# queso_dip_v4_7.net
KiCad netlist of a schematic drawn in EAGLE
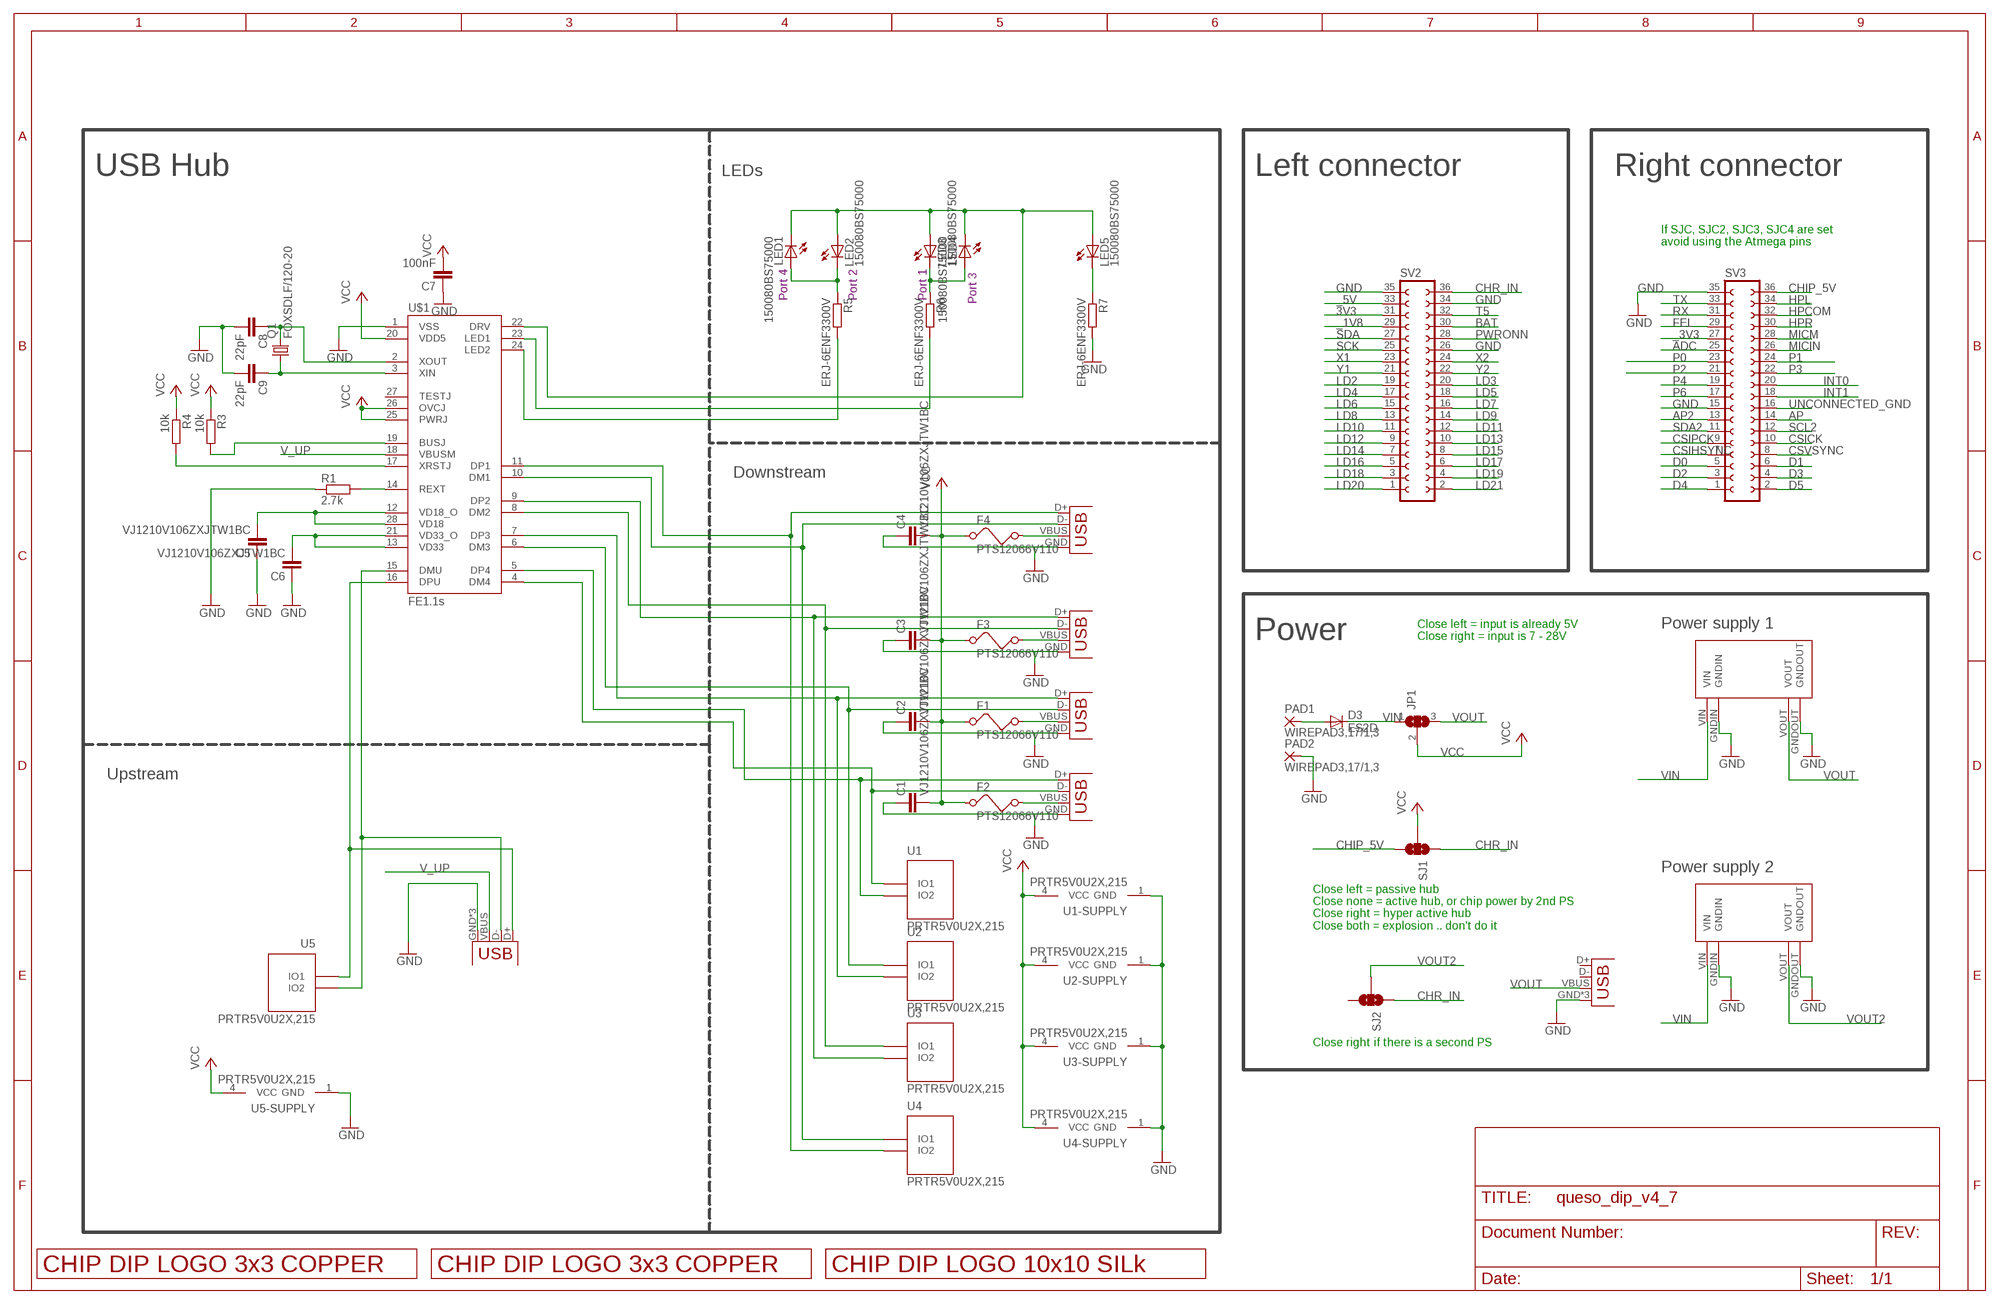
[diagram p0: schematic, sheet 1]

(export (version "E")
  (design (tool "Eeschema 10.0.6"))
  (components
    (comp (ref "C1")
      (value "VJ1210V106ZXJTW1BC")
      (footprint "eagle-import:C1210")
      (libsource (lib "eagle-import") (part "C-EUC1210"))
    )
    (comp (ref "C2")
      (value "VJ1210V106ZXJTW1BC")
      (footprint "eagle-import:C1210")
      (libsource (lib "eagle-import") (part "C-EUC1210"))
    )
    (comp (ref "C3")
      (value "VJ1210V106ZXJTW1BC")
      (footprint "eagle-import:C1210")
      (libsource (lib "eagle-import") (part "C-EUC1210"))
    )
    (comp (ref "C4")
      (value "VJ1210V106ZXJTW1BC")
      (footprint "eagle-import:C1210")
      (libsource (lib "eagle-import") (part "C-EUC1210"))
    )
    (comp (ref "C5")
      (value "VJ1210V106ZXJTW1BC")
      (footprint "eagle-import:C1210")
      (libsource (lib "eagle-import") (part "C-EUC1210"))
    )
    (comp (ref "C6")
      (value "VJ1210V106ZXJTW1BC")
      (footprint "eagle-import:C1210")
      (libsource (lib "eagle-import") (part "C-EUC1210"))
    )
    (comp (ref "C7")
      (value "100nF")
      (footprint "eagle-import:C0805")
      (libsource (lib "eagle-import") (part "C-EUC0805"))
    )
    (comp (ref "C8")
      (value "22pF")
      (footprint "eagle-import:C0805")
      (libsource (lib "eagle-import") (part "C-EUC0805"))
    )
    (comp (ref "C9")
      (value "22pF")
      (footprint "eagle-import:C0805")
      (libsource (lib "eagle-import") (part "C-EUC0805"))
    )
    (comp (ref "D3")
      (value "ES2D")
      (footprint "eagle-import:SMB")
      (libsource (lib "eagle-import") (part "ES2D"))
    )
    (comp (ref "F1")
      (value "PTS12066V110")
      (footprint "eagle-import:1210")
      (libsource (lib "eagle-import") (part "FUSED"))
    )
    (comp (ref "F2")
      (value "PTS12066V110")
      (footprint "eagle-import:1210")
      (libsource (lib "eagle-import") (part "FUSED"))
    )
    (comp (ref "F3")
      (value "PTS12066V110")
      (footprint "eagle-import:1210")
      (libsource (lib "eagle-import") (part "FUSED"))
    )
    (comp (ref "F4")
      (value "PTS12066V110")
      (footprint "eagle-import:1210")
      (libsource (lib "eagle-import") (part "FUSED"))
    )
    (comp (ref "JP1")
      (value "SJ2W")
      (footprint "eagle-import:SJ_2")
      (libsource (lib "eagle-import") (part "SJ2W"))
    )
    (comp (ref "LED1")
      (value "150080BS75000")
      (footprint "eagle-import:CHIP-LED0805")
      (libsource (lib "eagle-import") (part "LEDCHIP-LED0805"))
    )
    (comp (ref "LED2")
      (value "150080BS75000")
      (footprint "eagle-import:CHIP-LED0805")
      (libsource (lib "eagle-import") (part "LEDCHIP-LED0805"))
    )
    (comp (ref "LED3")
      (value "150080BS75000")
      (footprint "eagle-import:CHIP-LED0805")
      (libsource (lib "eagle-import") (part "LEDCHIP-LED0805"))
    )
    (comp (ref "LED4")
      (value "150080BS75000")
      (footprint "eagle-import:CHIP-LED0805")
      (libsource (lib "eagle-import") (part "LEDCHIP-LED0805"))
    )
    (comp (ref "LED5")
      (value "150080BS75000")
      (footprint "eagle-import:CHIP-LED0805")
      (libsource (lib "eagle-import") (part "LEDCHIP-LED0805"))
    )
    (comp (ref "PAD1")
      (value "WIREPAD3,17/1,3")
      (footprint "eagle-import:3,17_1,3")
      (libsource (lib "eagle-import") (part "WIREPAD3,17/1,3"))
    )
    (comp (ref "PAD2")
      (value "WIREPAD3,17/1,3")
      (footprint "eagle-import:3,17_1,3")
      (libsource (lib "eagle-import") (part "WIREPAD3,17/1,3"))
    )
    (comp (ref "Q1")
      (value "FOXSDLF/120-20")
      (footprint "eagle-import:SM49")
      (libsource (lib "eagle-import") (part "CRYSTALSM49"))
    )
    (comp (ref "R1")
      (value "2.7k")
      (footprint "eagle-import:R0805")
      (libsource (lib "eagle-import") (part "R-EU_R0805"))
    )
    (comp (ref "R3")
      (value "10k")
      (footprint "eagle-import:R0805")
      (libsource (lib "eagle-import") (part "R-EU_R0805"))
    )
    (comp (ref "R4")
      (value "10k")
      (footprint "eagle-import:R0805")
      (libsource (lib "eagle-import") (part "R-EU_R0805"))
    )
    (comp (ref "R5")
      (value "ERJ-6ENF3300V")
      (footprint "eagle-import:R0805")
      (libsource (lib "eagle-import") (part "R-EU_R0805"))
    )
    (comp (ref "R6")
      (value "ERJ-6ENF3300V")
      (footprint "eagle-import:R0805")
      (libsource (lib "eagle-import") (part "R-EU_R0805"))
    )
    (comp (ref "R7")
      (value "ERJ-6ENF3300V")
      (footprint "eagle-import:R0805")
      (libsource (lib "eagle-import") (part "R-EU_R0805"))
    )
    (comp (ref "SJ1")
      (value "SOLDERJUMPER_2WAYT")
      (footprint "eagle-import:SJ_2")
      (libsource (lib "eagle-import") (part "SOLDERJUMPER_2WAYT"))
    )
    (comp (ref "SJ2")
      (value "SOLDERJUMPER_2WAYT")
      (footprint "eagle-import:SJ_2")
      (libsource (lib "eagle-import") (part "SOLDERJUMPER_2WAYT"))
    )
    (comp (ref "SV2")
      (value "FE18-2")
      (footprint "eagle-import:FE18-2")
      (libsource (lib "eagle-import") (part "FE18-2"))
    )
    (comp (ref "SV3")
      (value "FE18-2")
      (footprint "eagle-import:FE18-2")
      (libsource (lib "eagle-import") (part "FE18-2"))
    )
    (comp (ref "U$1")
      (value "FE1.1S")
      (footprint "eagle-import:FE1.1S_SSOP-28")
      (libsource (lib "eagle-import") (part "FE1.1S"))
    )
    (comp (ref "U$2")
      (value "LOGO_3X3_COPPER")
      (footprint "eagle-import:LOGO_3X3_COPPER")
      (libsource (lib "eagle-import") (part "LOGO_3X3_COPPER"))
    )
    (comp (ref "U$3")
      (value "MP1584EN")
      (footprint "eagle-import:MP1584EN")
      (libsource (lib "eagle-import") (part "MP1584EN"))
    )
    (comp (ref "U$4")
      (value "LOGO_3X3_COPPER")
      (footprint "eagle-import:LOGO_3X3_COPPER")
      (libsource (lib "eagle-import") (part "LOGO_3X3_COPPER"))
    )
    (comp (ref "U$5")
      (value "LOGO_10X10_SILK")
      (footprint "eagle-import:LOGO_10X10_SILK")
      (libsource (lib "eagle-import") (part "LOGO_10X10_SILK"))
    )
    (comp (ref "U$9")
      (value "MP1584EN")
      (footprint "eagle-import:MP1584EN")
      (libsource (lib "eagle-import") (part "MP1584EN"))
    )
    (comp (ref "U1")
      (value "PRTR5V0U2X,215")
      (footprint "eagle-import:SOT-143B")
      (fields (field (name "MANUFACTURER") "NXP Semiconductors"))
      (libsource (lib "eagle-import") (part "PRTR5V0U2X?"))
    )
    (comp (ref "U2")
      (value "PRTR5V0U2X,215")
      (footprint "eagle-import:SOT-143B")
      (fields (field (name "MANUFACTURER") "NXP Semiconductors"))
      (libsource (lib "eagle-import") (part "PRTR5V0U2X?"))
    )
    (comp (ref "U3")
      (value "PRTR5V0U2X,215")
      (footprint "eagle-import:SOT-143B")
      (fields (field (name "MANUFACTURER") "NXP Semiconductors"))
      (libsource (lib "eagle-import") (part "PRTR5V0U2X?"))
    )
    (comp (ref "U4")
      (value "PRTR5V0U2X,215")
      (footprint "eagle-import:SOT-143B")
      (fields (field (name "MANUFACTURER") "NXP Semiconductors"))
      (libsource (lib "eagle-import") (part "PRTR5V0U2X?"))
    )
    (comp (ref "U5")
      (value "PRTR5V0U2X,215")
      (footprint "eagle-import:SOT-143B")
      (fields (field (name "MANUFACTURER") "NXP Semiconductors"))
      (libsource (lib "eagle-import") (part "PRTR5V0U2X?"))
    )
    (comp (ref "USB")
      (value "USBUSB-MICROB-SMT-DIP")
      (footprint "eagle-import:USB-MICROB-SMT-DIP")
      (libsource (lib "eagle-import") (part "USBUSB-MICROB-SMT-DIP"))
    )
    (comp (ref "USB1")
      (value "USBUSB-MICROB-SMT-DIP")
      (footprint "eagle-import:USB-MICROB-SMT-DIP")
      (libsource (lib "eagle-import") (part "USBUSB-MICROB-SMT-DIP"))
    )
    (comp (ref "X1")
      (value "USB-A-S")
      (footprint "eagle-import:USB-A-S")
      (libsource (lib "eagle-import") (part "con-usb_USB-A-S"))
    )
    (comp (ref "X2")
      (value "USB-A-S")
      (footprint "eagle-import:USB-A-S")
      (libsource (lib "eagle-import") (part "con-usb_USB-A-S"))
    )
    (comp (ref "X3")
      (value "USB-A-S")
      (footprint "eagle-import:USB-A-S")
      (libsource (lib "eagle-import") (part "con-usb_USB-A-S"))
    )
    (comp (ref "X4")
      (value "USB-A-S")
      (footprint "eagle-import:USB-A-S")
      (libsource (lib "eagle-import") (part "con-usb_USB-A-S"))
    )
  )
  (nets
    (net (code "1") (name "/3V3") (class "Default")
      (node (ref "SV2") (pin "31") (pinfunction "31_31") (pintype "passive"))
    )
    (net (code "2") (name "/ADC") (class "Default")
      (node (ref "SV3") (pin "25") (pinfunction "25_25") (pintype "passive"))
    )
    (net (code "3") (name "/AP") (class "Default")
      (node (ref "SV3") (pin "14") (pinfunction "14_14") (pintype "passive"))
    )
    (net (code "4") (name "/AP2") (class "Default")
      (node (ref "SV3") (pin "13") (pinfunction "13_13") (pintype "passive"))
    )
    (net (code "5") (name "/BAT") (class "Default")
      (node (ref "SV2") (pin "30") (pinfunction "30_30") (pintype "passive"))
    )
    (net (code "6") (name "/CHIP_5V") (class "Default")
      (node (ref "SJ1") (pin "3") (pinfunction "3_3") (pintype "passive"))
      (node (ref "SV3") (pin "36") (pinfunction "36_36") (pintype "passive"))
    )
    (net (code "7") (name "/CHR_IN") (class "Default")
      (node (ref "SJ1") (pin "1") (pinfunction "1_1") (pintype "passive"))
      (node (ref "SJ2") (pin "1") (pinfunction "1_1") (pintype "passive"))
      (node (ref "SV2") (pin "36") (pinfunction "36_36") (pintype "passive"))
    )
    (net (code "8") (name "/CSICK") (class "Default")
      (node (ref "SV3") (pin "10") (pinfunction "10_10") (pintype "passive"))
    )
    (net (code "9") (name "/CSIHSYNC") (class "Default")
      (node (ref "SV3") (pin "7") (pinfunction "7_7") (pintype "passive"))
    )
    (net (code "10") (name "/CSIPCK") (class "Default")
      (node (ref "SV3") (pin "9") (pinfunction "9_9") (pintype "passive"))
    )
    (net (code "11") (name "/CSVSYNC") (class "Default")
      (node (ref "SV3") (pin "8") (pinfunction "8_8") (pintype "passive"))
    )
    (net (code "12") (name "/D0") (class "Default")
      (node (ref "SV3") (pin "5") (pinfunction "5_5") (pintype "passive"))
    )
    (net (code "13") (name "/D1") (class "Default")
      (node (ref "SV3") (pin "6") (pinfunction "6_6") (pintype "passive"))
    )
    (net (code "14") (name "/D2") (class "Default")
      (node (ref "SV3") (pin "3") (pinfunction "3_3") (pintype "passive"))
    )
    (net (code "15") (name "/D3") (class "Default")
      (node (ref "SV3") (pin "4") (pinfunction "4_4") (pintype "passive"))
    )
    (net (code "16") (name "/D4") (class "Default")
      (node (ref "SV3") (pin "1") (pinfunction "1_1") (pintype "passive"))
    )
    (net (code "17") (name "/D5") (class "Default")
      (node (ref "SV3") (pin "2") (pinfunction "2_2") (pintype "passive"))
    )
    (net (code "18") (name "/FEL") (class "Default")
      (node (ref "SV3") (pin "29") (pinfunction "29_29") (pintype "passive"))
    )
    (net (code "19") (name "/HPCOM") (class "Default")
      (node (ref "SV3") (pin "32") (pinfunction "32_32") (pintype "passive"))
    )
    (net (code "20") (name "/HPL") (class "Default")
      (node (ref "SV3") (pin "34") (pinfunction "34_34") (pintype "passive"))
    )
    (net (code "21") (name "/HPR") (class "Default")
      (node (ref "SV3") (pin "30") (pinfunction "30_30") (pintype "passive"))
    )
    (net (code "22") (name "/INT0") (class "Default")
      (node (ref "SV3") (pin "20") (pinfunction "20_20") (pintype "passive"))
    )
    (net (code "23") (name "/INT1") (class "Default")
      (node (ref "SV3") (pin "18") (pinfunction "18_18") (pintype "passive"))
    )
    (net (code "24") (name "/LD2") (class "Default")
      (node (ref "SV2") (pin "19") (pinfunction "19_19") (pintype "passive"))
    )
    (net (code "25") (name "/LD3") (class "Default")
      (node (ref "SV2") (pin "20") (pinfunction "20_20") (pintype "passive"))
    )
    (net (code "26") (name "/LD4") (class "Default")
      (node (ref "SV2") (pin "17") (pinfunction "17_17") (pintype "passive"))
    )
    (net (code "27") (name "/LD5") (class "Default")
      (node (ref "SV2") (pin "18") (pinfunction "18_18") (pintype "passive"))
    )
    (net (code "28") (name "/LD6") (class "Default")
      (node (ref "SV2") (pin "15") (pinfunction "15_15") (pintype "passive"))
    )
    (net (code "29") (name "/LD7") (class "Default")
      (node (ref "SV2") (pin "16") (pinfunction "16_16") (pintype "passive"))
    )
    (net (code "30") (name "/LD8") (class "Default")
      (node (ref "SV2") (pin "13") (pinfunction "13_13") (pintype "passive"))
    )
    (net (code "31") (name "/LD9") (class "Default")
      (node (ref "SV2") (pin "14") (pinfunction "14_14") (pintype "passive"))
    )
    (net (code "32") (name "/LD10") (class "Default")
      (node (ref "SV2") (pin "11") (pinfunction "11_11") (pintype "passive"))
    )
    (net (code "33") (name "/LD11") (class "Default")
      (node (ref "SV2") (pin "12") (pinfunction "12_12") (pintype "passive"))
    )
    (net (code "34") (name "/LD12") (class "Default")
      (node (ref "SV2") (pin "9") (pinfunction "9_9") (pintype "passive"))
    )
    (net (code "35") (name "/LD13") (class "Default")
      (node (ref "SV2") (pin "10") (pinfunction "10_10") (pintype "passive"))
    )
    (net (code "36") (name "/LD14") (class "Default")
      (node (ref "SV2") (pin "7") (pinfunction "7_7") (pintype "passive"))
    )
    (net (code "37") (name "/LD15") (class "Default")
      (node (ref "SV2") (pin "8") (pinfunction "8_8") (pintype "passive"))
    )
    (net (code "38") (name "/LD16") (class "Default")
      (node (ref "SV2") (pin "5") (pinfunction "5_5") (pintype "passive"))
    )
    (net (code "39") (name "/LD17") (class "Default")
      (node (ref "SV2") (pin "6") (pinfunction "6_6") (pintype "passive"))
    )
    (net (code "40") (name "/LD18") (class "Default")
      (node (ref "SV2") (pin "3") (pinfunction "3_3") (pintype "passive"))
    )
    (net (code "41") (name "/LD19") (class "Default")
      (node (ref "SV2") (pin "4") (pinfunction "4_4") (pintype "passive"))
    )
    (net (code "42") (name "/LD20") (class "Default")
      (node (ref "SV2") (pin "1") (pinfunction "1_1") (pintype "passive"))
    )
    (net (code "43") (name "/LD21") (class "Default")
      (node (ref "SV2") (pin "2") (pinfunction "2_2") (pintype "passive"))
    )
    (net (code "44") (name "/MICIN") (class "Default")
      (node (ref "SV3") (pin "26") (pinfunction "26_26") (pintype "passive"))
    )
    (net (code "45") (name "/MICM") (class "Default")
      (node (ref "SV3") (pin "28") (pinfunction "28_28") (pintype "passive"))
    )
    (net (code "46") (name "/P0") (class "Default")
      (node (ref "SV3") (pin "23") (pinfunction "23_23") (pintype "passive"))
    )
    (net (code "47") (name "/P1") (class "Default")
      (node (ref "SV3") (pin "24") (pinfunction "24_24") (pintype "passive"))
    )
    (net (code "48") (name "/P2") (class "Default")
      (node (ref "SV3") (pin "21") (pinfunction "21_21") (pintype "passive"))
    )
    (net (code "49") (name "/P3") (class "Default")
      (node (ref "SV3") (pin "22") (pinfunction "22_22") (pintype "passive"))
    )
    (net (code "50") (name "/P4") (class "Default")
      (node (ref "SV3") (pin "19") (pinfunction "19_19") (pintype "passive"))
    )
    (net (code "51") (name "/P6") (class "Default")
      (node (ref "SV3") (pin "17") (pinfunction "17_17") (pintype "passive"))
    )
    (net (code "52") (name "/PWRONN") (class "Default")
      (node (ref "SV2") (pin "28") (pinfunction "28_28") (pintype "passive"))
    )
    (net (code "53") (name "/RX") (class "Default")
      (node (ref "SV3") (pin "31") (pinfunction "31_31") (pintype "passive"))
    )
    (net (code "54") (name "/SCK") (class "Default")
      (node (ref "SV2") (pin "25") (pinfunction "25_25") (pintype "passive"))
    )
    (net (code "55") (name "/SCL2") (class "Default")
      (node (ref "SV3") (pin "12") (pinfunction "12_12") (pintype "passive"))
    )
    (net (code "56") (name "/SDA") (class "Default")
      (node (ref "SV2") (pin "27") (pinfunction "27_27") (pintype "passive"))
    )
    (net (code "57") (name "/SDA2") (class "Default")
      (node (ref "SV3") (pin "11") (pinfunction "11_11") (pintype "passive"))
    )
    (net (code "58") (name "/T5") (class "Default")
      (node (ref "SV2") (pin "32") (pinfunction "32_32") (pintype "passive"))
    )
    (net (code "59") (name "/TX") (class "Default")
      (node (ref "SV3") (pin "33") (pinfunction "33_33") (pintype "passive"))
    )
    (net (code "60") (name "/UNCONNECTED_GND") (class "Default")
      (node (ref "SV3") (pin "16") (pinfunction "16_16") (pintype "passive"))
    )
    (net (code "61") (name "/VIN") (class "Default")
      (node (ref "D3") (pin "C") (pinfunction "C_C") (pintype "passive"))
      (node (ref "JP1") (pin "1") (pinfunction "1_1") (pintype "passive"))
      (node (ref "U$3") (pin "VIN") (pinfunction "VIN_VIN") (pintype "power_in"))
      (node (ref "U$9") (pin "VIN") (pinfunction "VIN_VIN") (pintype "power_in"))
    )
    (net (code "62") (name "/VOUT") (class "Default")
      (node (ref "JP1") (pin "3") (pinfunction "3_3") (pintype "passive"))
      (node (ref "U$9") (pin "VOUT") (pinfunction "VOUT_VOUT") (pintype "power_in"))
      (node (ref "USB1") (pin "VBUS") (pinfunction "VBUS_VBUS") (pintype "bidirectional"))
    )
    (net (code "63") (name "/VOUT2") (class "Default")
      (node (ref "SJ2") (pin "2") (pinfunction "2_2") (pintype "passive"))
      (node (ref "U$3") (pin "VOUT") (pinfunction "VOUT_VOUT") (pintype "power_in"))
    )
    (net (code "64") (name "/V_UP") (class "Default")
      (node (ref "U$1") (pin "18") (pinfunction "VBUSM_18") (pintype "bidirectional"))
      (node (ref "USB") (pin "VBUS") (pinfunction "VBUS_VBUS") (pintype "bidirectional"))
    )
    (net (code "65") (name "/X1") (class "Default")
      (node (ref "SV2") (pin "23") (pinfunction "23_23") (pintype "passive"))
    )
    (net (code "66") (name "/X2") (class "Default")
      (node (ref "SV2") (pin "24") (pinfunction "24_24") (pintype "passive"))
    )
    (net (code "67") (name "/Y1") (class "Default")
      (node (ref "SV2") (pin "21") (pinfunction "21_21") (pintype "passive"))
    )
    (net (code "68") (name "/Y2") (class "Default")
      (node (ref "SV2") (pin "22") (pinfunction "22_22") (pintype "passive"))
    )
    (net (code "69") (name "/_1V8") (class "Default")
      (node (ref "SV2") (pin "29") (pinfunction "29_29") (pintype "passive"))
    )
    (net (code "70") (name "/_3V3") (class "Default")
      (node (ref "SV3") (pin "27") (pinfunction "27_27") (pintype "passive"))
    )
    (net (code "71") (name "/_5V") (class "Default")
      (node (ref "SV2") (pin "33") (pinfunction "33_33") (pintype "passive"))
    )
    (net (code "72") (name "GND") (class "Default")
      (node (ref "C1") (pin "1") (pinfunction "1_1") (pintype "passive"))
      (node (ref "C2") (pin "1") (pinfunction "1_1") (pintype "passive"))
      (node (ref "C3") (pin "1") (pinfunction "1_1") (pintype "passive"))
      (node (ref "C4") (pin "1") (pinfunction "1_1") (pintype "passive"))
      (node (ref "C5") (pin "1") (pinfunction "1_1") (pintype "passive"))
      (node (ref "C6") (pin "1") (pinfunction "1_1") (pintype "passive"))
      (node (ref "C7") (pin "1") (pinfunction "1_1") (pintype "passive"))
      (node (ref "C8") (pin "2") (pinfunction "2_2") (pintype "passive"))
      (node (ref "C9") (pin "2") (pinfunction "2_2") (pintype "passive"))
      (node (ref "PAD2") (pin "1") (pinfunction "P_1") (pintype "passive"))
      (node (ref "R1") (pin "1") (pinfunction "1_1") (pintype "passive"))
      (node (ref "R7") (pin "2") (pinfunction "2_2") (pintype "passive"))
      (node (ref "SV2") (pin "26") (pinfunction "26_26") (pintype "passive"))
      (node (ref "SV2") (pin "34") (pinfunction "34_34") (pintype "passive"))
      (node (ref "SV2") (pin "35") (pinfunction "35_35") (pintype "passive"))
      (node (ref "SV3") (pin "15") (pinfunction "15_15") (pintype "passive"))
      (node (ref "SV3") (pin "35") (pinfunction "35_35") (pintype "passive"))
      (node (ref "U$1") (pin "1") (pinfunction "VSS_1") (pintype "bidirectional"))
      (node (ref "U$3") (pin "GNDIN") (pinfunction "GNDIN_GNDIN") (pintype "power_in"))
      (node (ref "U$3") (pin "GNDOUT") (pinfunction "GNDOUT_GNDOUT") (pintype "power_in"))
      (node (ref "U$9") (pin "GNDIN") (pinfunction "GNDIN_GNDIN") (pintype "power_in"))
      (node (ref "U$9") (pin "GNDOUT") (pinfunction "GNDOUT_GNDOUT") (pintype "power_in"))
      (node (ref "U1") (pin "1") (pinfunction "GND_1") (pintype "bidirectional"))
      (node (ref "U2") (pin "1") (pinfunction "GND_1") (pintype "bidirectional"))
      (node (ref "U3") (pin "1") (pinfunction "GND_1") (pintype "bidirectional"))
      (node (ref "U4") (pin "1") (pinfunction "GND_1") (pintype "bidirectional"))
      (node (ref "U5") (pin "1") (pinfunction "GND_1") (pintype "bidirectional"))
      (node (ref "USB") (pin "GND") (pinfunction "GND_GND") (pintype "bidirectional"))
      (node (ref "USB") (pin "MT1") (pinfunction "GND_MT1") (pintype "bidirectional"))
      (node (ref "USB") (pin "MT2") (pinfunction "GND_MT2") (pintype "bidirectional"))
      (node (ref "USB1") (pin "GND") (pinfunction "GND_GND") (pintype "bidirectional"))
      (node (ref "USB1") (pin "MT1") (pinfunction "GND_MT1") (pintype "bidirectional"))
      (node (ref "USB1") (pin "MT2") (pinfunction "GND_MT2") (pintype "bidirectional"))
      (node (ref "X1") (pin "GND") (pinfunction "GND_GND") (pintype "bidirectional"))
      (node (ref "X2") (pin "GND") (pinfunction "GND_GND") (pintype "bidirectional"))
      (node (ref "X3") (pin "GND") (pinfunction "GND_GND") (pintype "bidirectional"))
      (node (ref "X4") (pin "GND") (pinfunction "GND_GND") (pintype "bidirectional"))
    )
    (net (code "73") (name "Net-(F1-Pad2)") (class "Default")
      (node (ref "F1") (pin "2") (pinfunction "2_2") (pintype "passive"))
      (node (ref "X2") (pin "VBUS") (pinfunction "VBUS_VBUS") (pintype "bidirectional"))
    )
    (net (code "74") (name "Net-(F2-Pad2)") (class "Default")
      (node (ref "F2") (pin "2") (pinfunction "2_2") (pintype "passive"))
      (node (ref "X1") (pin "VBUS") (pinfunction "VBUS_VBUS") (pintype "bidirectional"))
    )
    (net (code "75") (name "Net-(F3-Pad2)") (class "Default")
      (node (ref "F3") (pin "2") (pinfunction "2_2") (pintype "passive"))
      (node (ref "X3") (pin "VBUS") (pinfunction "VBUS_VBUS") (pintype "bidirectional"))
    )
    (net (code "76") (name "Net-(F4-Pad2)") (class "Default")
      (node (ref "F4") (pin "2") (pinfunction "2_2") (pintype "passive"))
      (node (ref "X4") (pin "VBUS") (pinfunction "VBUS_VBUS") (pintype "bidirectional"))
    )
    (net (code "77") (name "Net-(LED1-PadA)") (class "Default")
      (node (ref "LED1") (pin "A") (pinfunction "A_A") (pintype "passive"))
      (node (ref "LED2") (pin "C") (pinfunction "C_C") (pintype "passive"))
      (node (ref "R5") (pin "1") (pinfunction "1_1") (pintype "passive"))
    )
    (net (code "78") (name "Net-(LED3-PadC)") (class "Default")
      (node (ref "LED3") (pin "C") (pinfunction "C_C") (pintype "passive"))
      (node (ref "LED4") (pin "A") (pinfunction "A_A") (pintype "passive"))
      (node (ref "R6") (pin "1") (pinfunction "1_1") (pintype "passive"))
    )
    (net (code "79") (name "Net-(LED5-PadC)") (class "Default")
      (node (ref "LED5") (pin "C") (pinfunction "C_C") (pintype "passive"))
      (node (ref "R7") (pin "1") (pinfunction "1_1") (pintype "passive"))
    )
    (net (code "80") (name "Net-(PAD1-P)") (class "Default")
      (node (ref "D3") (pin "A") (pinfunction "A_A") (pintype "passive"))
      (node (ref "PAD1") (pin "1") (pinfunction "P_1") (pintype "passive"))
    )
    (net (code "81") (name "Net-(U$1-BUSJ)") (class "Default")
      (node (ref "R3") (pin "2") (pinfunction "2_2") (pintype "passive"))
      (node (ref "U$1") (pin "19") (pinfunction "BUSJ_19") (pintype "bidirectional"))
    )
    (net (code "82") (name "Net-(U$1-DM1)") (class "Default")
      (node (ref "U$1") (pin "10") (pinfunction "DM1_10") (pintype "bidirectional"))
      (node (ref "U4") (pin "2") (pinfunction "IO1_2") (pintype "bidirectional"))
      (node (ref "X4") (pin "D-") (pinfunction "D-_D-") (pintype "bidirectional"))
    )
    (net (code "83") (name "Net-(U$1-DM2)") (class "Default")
      (node (ref "U$1") (pin "8") (pinfunction "DM2_8") (pintype "bidirectional"))
      (node (ref "U3") (pin "2") (pinfunction "IO1_2") (pintype "bidirectional"))
      (node (ref "X3") (pin "D-") (pinfunction "D-_D-") (pintype "bidirectional"))
    )
    (net (code "84") (name "Net-(U$1-DM3)") (class "Default")
      (node (ref "U$1") (pin "6") (pinfunction "DM3_6") (pintype "bidirectional"))
      (node (ref "U2") (pin "2") (pinfunction "IO1_2") (pintype "bidirectional"))
      (node (ref "X2") (pin "D-") (pinfunction "D-_D-") (pintype "bidirectional"))
    )
    (net (code "85") (name "Net-(U$1-DM4)") (class "Default")
      (node (ref "U$1") (pin "4") (pinfunction "DM4_4") (pintype "bidirectional"))
      (node (ref "U1") (pin "2") (pinfunction "IO1_2") (pintype "bidirectional"))
      (node (ref "X1") (pin "D-") (pinfunction "D-_D-") (pintype "bidirectional"))
    )
    (net (code "86") (name "Net-(U$1-DMU)") (class "Default")
      (node (ref "U$1") (pin "15") (pinfunction "DMU_15") (pintype "bidirectional"))
      (node (ref "U5") (pin "3") (pinfunction "IO2_3") (pintype "bidirectional"))
      (node (ref "USB") (pin "D-") (pinfunction "D-_D-") (pintype "bidirectional"))
    )
    (net (code "87") (name "Net-(U$1-DP1)") (class "Default")
      (node (ref "U$1") (pin "11") (pinfunction "DP1_11") (pintype "bidirectional"))
      (node (ref "U4") (pin "3") (pinfunction "IO2_3") (pintype "bidirectional"))
      (node (ref "X4") (pin "D+") (pinfunction "D+_D+") (pintype "bidirectional"))
    )
    (net (code "88") (name "Net-(U$1-DP2)") (class "Default")
      (node (ref "U$1") (pin "9") (pinfunction "DP2_9") (pintype "bidirectional"))
      (node (ref "U3") (pin "3") (pinfunction "IO2_3") (pintype "bidirectional"))
      (node (ref "X3") (pin "D+") (pinfunction "D+_D+") (pintype "bidirectional"))
    )
    (net (code "89") (name "Net-(U$1-DP3)") (class "Default")
      (node (ref "U$1") (pin "7") (pinfunction "DP3_7") (pintype "bidirectional"))
      (node (ref "U2") (pin "3") (pinfunction "IO2_3") (pintype "bidirectional"))
      (node (ref "X2") (pin "D+") (pinfunction "D+_D+") (pintype "bidirectional"))
    )
    (net (code "90") (name "Net-(U$1-DP4)") (class "Default")
      (node (ref "U$1") (pin "5") (pinfunction "DP4_5") (pintype "bidirectional"))
      (node (ref "U1") (pin "3") (pinfunction "IO2_3") (pintype "bidirectional"))
      (node (ref "X1") (pin "D+") (pinfunction "D+_D+") (pintype "bidirectional"))
    )
    (net (code "91") (name "Net-(U$1-DPU)") (class "Default")
      (node (ref "U$1") (pin "16") (pinfunction "DPU_16") (pintype "bidirectional"))
      (node (ref "U5") (pin "2") (pinfunction "IO1_2") (pintype "bidirectional"))
      (node (ref "USB") (pin "D+") (pinfunction "D+_D+") (pintype "bidirectional"))
    )
    (net (code "92") (name "Net-(U$1-DRV)") (class "Default")
      (node (ref "LED1") (pin "C") (pinfunction "C_C") (pintype "passive"))
      (node (ref "LED2") (pin "A") (pinfunction "A_A") (pintype "passive"))
      (node (ref "LED3") (pin "A") (pinfunction "A_A") (pintype "passive"))
      (node (ref "LED4") (pin "C") (pinfunction "C_C") (pintype "passive"))
      (node (ref "LED5") (pin "A") (pinfunction "A_A") (pintype "passive"))
      (node (ref "U$1") (pin "22") (pinfunction "DRV_22") (pintype "bidirectional"))
    )
    (net (code "93") (name "Net-(U$1-LED1)") (class "Default")
      (node (ref "R6") (pin "2") (pinfunction "2_2") (pintype "passive"))
      (node (ref "U$1") (pin "23") (pinfunction "LED1_23") (pintype "bidirectional"))
    )
    (net (code "94") (name "Net-(U$1-LED2)") (class "Default")
      (node (ref "R5") (pin "2") (pinfunction "2_2") (pintype "passive"))
      (node (ref "U$1") (pin "24") (pinfunction "LED2_24") (pintype "bidirectional"))
    )
    (net (code "95") (name "Net-(U$1-REXT)") (class "Default")
      (node (ref "R1") (pin "2") (pinfunction "2_2") (pintype "passive"))
      (node (ref "U$1") (pin "14") (pinfunction "REXT_14") (pintype "bidirectional"))
    )
    (net (code "96") (name "Net-(U$1-VD18)") (class "Default")
      (node (ref "C5") (pin "2") (pinfunction "2_2") (pintype "passive"))
      (node (ref "U$1") (pin "12") (pinfunction "VD18_O_12") (pintype "bidirectional"))
      (node (ref "U$1") (pin "28") (pinfunction "VD18_28") (pintype "bidirectional"))
    )
    (net (code "97") (name "Net-(U$1-VD33)") (class "Default")
      (node (ref "C6") (pin "2") (pinfunction "2_2") (pintype "passive"))
      (node (ref "U$1") (pin "13") (pinfunction "VD33_13") (pintype "bidirectional"))
      (node (ref "U$1") (pin "21") (pinfunction "VD33_O_21") (pintype "bidirectional"))
    )
    (net (code "98") (name "Net-(U$1-XIN)") (class "Default")
      (node (ref "C9") (pin "1") (pinfunction "1_1") (pintype "passive"))
      (node (ref "Q1") (pin "1") (pinfunction "1_1") (pintype "passive"))
      (node (ref "U$1") (pin "3") (pinfunction "XIN_3") (pintype "bidirectional"))
    )
    (net (code "99") (name "Net-(U$1-XOUT)") (class "Default")
      (node (ref "C8") (pin "1") (pinfunction "1_1") (pintype "passive"))
      (node (ref "Q1") (pin "2") (pinfunction "2_2") (pintype "passive"))
      (node (ref "U$1") (pin "2") (pinfunction "XOUT_2") (pintype "bidirectional"))
    )
    (net (code "100") (name "Net-(U$1-XRSTJ)") (class "Default")
      (node (ref "R4") (pin "2") (pinfunction "2_2") (pintype "passive"))
      (node (ref "U$1") (pin "17") (pinfunction "XRSTJ_17") (pintype "bidirectional"))
    )
    (net (code "101") (name "VCC") (class "Default")
      (node (ref "C1") (pin "2") (pinfunction "2_2") (pintype "passive"))
      (node (ref "C2") (pin "2") (pinfunction "2_2") (pintype "passive"))
      (node (ref "C3") (pin "2") (pinfunction "2_2") (pintype "passive"))
      (node (ref "C4") (pin "2") (pinfunction "2_2") (pintype "passive"))
      (node (ref "C7") (pin "2") (pinfunction "2_2") (pintype "passive"))
      (node (ref "F1") (pin "1") (pinfunction "1_1") (pintype "passive"))
      (node (ref "F2") (pin "1") (pinfunction "1_1") (pintype "passive"))
      (node (ref "F3") (pin "1") (pinfunction "1_1") (pintype "passive"))
      (node (ref "F4") (pin "1") (pinfunction "1_1") (pintype "passive"))
      (node (ref "JP1") (pin "2") (pinfunction "2_2") (pintype "passive"))
      (node (ref "R3") (pin "1") (pinfunction "1_1") (pintype "passive"))
      (node (ref "R4") (pin "1") (pinfunction "1_1") (pintype "passive"))
      (node (ref "SJ1") (pin "2") (pinfunction "2_2") (pintype "passive"))
      (node (ref "U$1") (pin "20") (pinfunction "VDD5_20") (pintype "bidirectional"))
      (node (ref "U$1") (pin "25") (pinfunction "PWRJ_25") (pintype "bidirectional"))
      (node (ref "U$1") (pin "26") (pinfunction "OVCJ_26") (pintype "bidirectional"))
      (node (ref "U1") (pin "4") (pinfunction "VCC_4") (pintype "bidirectional"))
      (node (ref "U2") (pin "4") (pinfunction "VCC_4") (pintype "bidirectional"))
      (node (ref "U3") (pin "4") (pinfunction "VCC_4") (pintype "bidirectional"))
      (node (ref "U4") (pin "4") (pinfunction "VCC_4") (pintype "bidirectional"))
      (node (ref "U5") (pin "4") (pinfunction "VCC_4") (pintype "bidirectional"))
    )
    (net (code "102") (name "unconnected-(SJ2-Pad3)") (class "Default")
      (node (ref "SJ2") (pin "3") (pinfunction "3_3") (pintype "passive"))
    )
    (net (code "103") (name "unconnected-(U$1-TESTJ-Pad27)") (class "Default")
      (node (ref "U$1") (pin "27") (pinfunction "TESTJ_27") (pintype "bidirectional"))
    )
    (net (code "104") (name "unconnected-(USB1-PadD+)") (class "Default")
      (node (ref "USB1") (pin "D+") (pinfunction "D+_D+") (pintype "bidirectional"))
    )
    (net (code "105") (name "unconnected-(USB1-PadD-)") (class "Default")
      (node (ref "USB1") (pin "D-") (pinfunction "D-_D-") (pintype "bidirectional"))
    )
  )
)
